# Regulator_Mechanical.net
KiCad netlist of a schematic drawn in Altium Designer
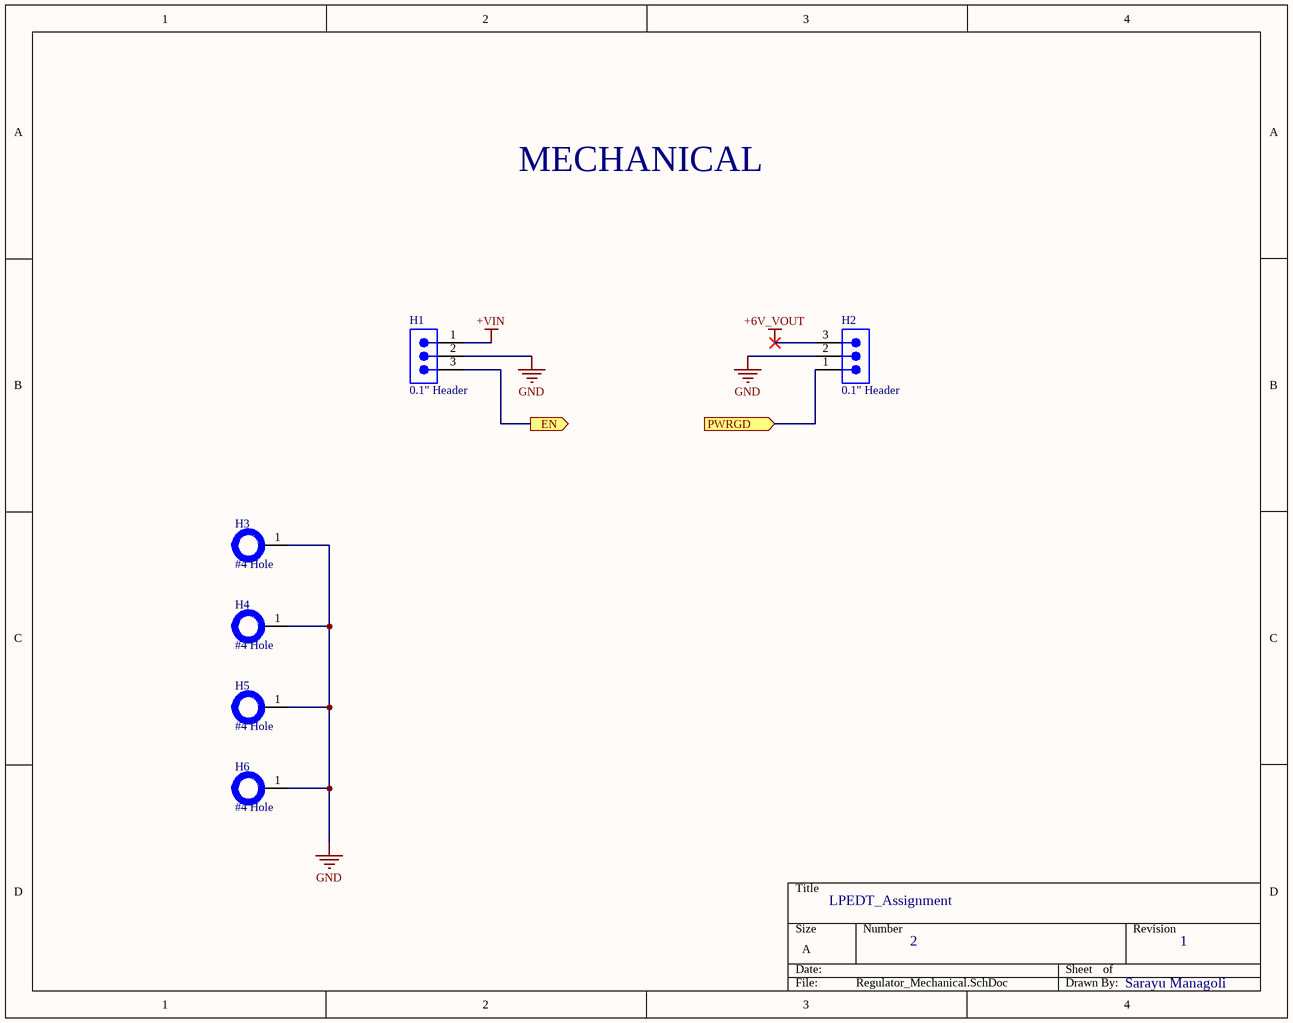
[diagram p0: Regulator_Mechanical.SchDoc]

(export (version "E")
  (design (tool "Eeschema 10.0.6"))
  (components
    (comp (ref "H1")
      (value "0.1\" Header")
      (footprint "3-PIN_MALE_HEADER_01-IN")
      (description "CONN HEADER VERT 3POS 2.54MM")
      (fields
        (field (name "MANUFACTURER") "Sullins")
        (field (name "MANUFACTURER PART NUMBER") "PRPC003SAAN-RC")
      )
      (libsource (lib "LPEDT_Parts") (part "PRPC003SAAN-RC"))
    )
    (comp (ref "H2")
      (value "0.1\" Header")
      (footprint "3-PIN_MALE_HEADER_01-IN")
      (description "CONN HEADER VERT 3POS 2.54MM")
      (fields
        (field (name "MANUFACTURER") "Sullins")
        (field (name "MANUFACTURER PART NUMBER") "PRPC003SAAN-RC")
      )
      (libsource (lib "LPEDT_Parts") (part "PRPC003SAAN-RC"))
    )
    (comp (ref "H3") (value "#4 Hole") (footprint "HOLE_#4") (libsource (lib "LPEDT_Parts") (part "HOLE_#4")))
    (comp (ref "H4") (value "#4 Hole") (footprint "HOLE_#4") (libsource (lib "LPEDT_Parts") (part "HOLE_#4")))
    (comp (ref "H5") (value "#4 Hole") (footprint "HOLE_#4") (libsource (lib "LPEDT_Parts") (part "HOLE_#4")))
    (comp (ref "H6") (value "#4 Hole") (footprint "HOLE_#4") (libsource (lib "LPEDT_Parts") (part "HOLE_#4")))
  )
  (nets
    (net (code "1") (name "+6V_VOUT") (class "Default")
      (node (ref "H2") (pin "3") (pinfunction "3_3") (pintype "passive"))
    )
    (net (code "2") (name "+VIN") (class "Default")
      (node (ref "H1") (pin "1") (pinfunction "1_1") (pintype "passive"))
    )
    (net (code "3") (name "/EN") (class "Default")
      (node (ref "H1") (pin "3") (pinfunction "3_3") (pintype "passive"))
    )
    (net (code "4") (name "/PWRGD") (class "Default")
      (node (ref "H2") (pin "1") (pinfunction "1_1") (pintype "passive"))
    )
    (net (code "5") (name "GND") (class "Default")
      (node (ref "H1") (pin "2") (pinfunction "2_2") (pintype "passive"))
      (node (ref "H2") (pin "2") (pinfunction "2_2") (pintype "passive"))
      (node (ref "H3") (pin "1") (pinfunction "1_1") (pintype "passive"))
      (node (ref "H4") (pin "1") (pinfunction "1_1") (pintype "passive"))
      (node (ref "H5") (pin "1") (pinfunction "1_1") (pintype "passive"))
      (node (ref "H6") (pin "1") (pinfunction "1_1") (pintype "passive"))
    )
  )
)
